# LTCSensorIndex.net
KiCad netlist of a schematic drawn in EAGLE
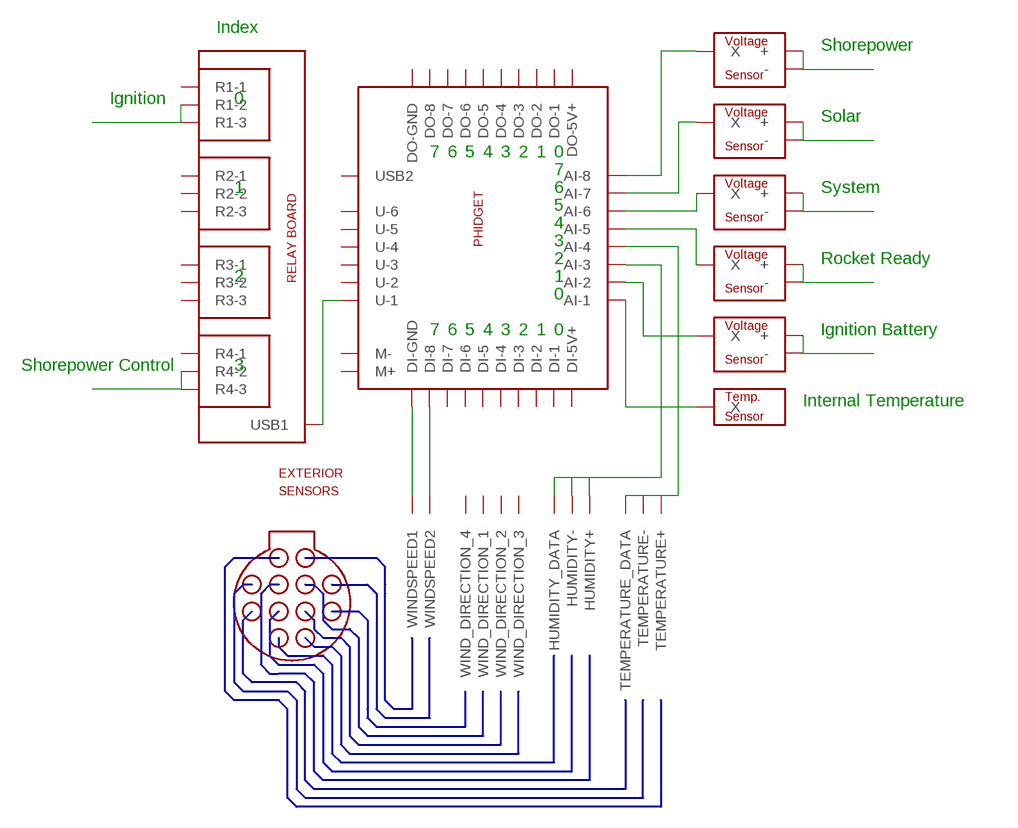
[diagram p0: schematic, sheet 1]

(export (version "E")
  (design (tool "Eeschema 10.0.6"))
  (components
    (comp (ref "U$1")
      (value "LAYOUT-PHIDGET")
      (footprint "eagle-import:LAYOUT-PACKAGE")
      (libsource (lib "eagle-import") (part "LAYOUT-PHIDGET"))
    )
    (comp (ref "U$2")
      (value "LAYOUT-SENSOR-TEMPERATURE")
      (footprint "eagle-import:LAYOUT-PACKAGE")
      (libsource (lib "eagle-import") (part "LAYOUT-SENSOR-TEMPERATURE"))
    )
    (comp (ref "U$3")
      (value "LAYOUT-SENSOR-VOLTAGE")
      (footprint "eagle-import:LAYOUT-PACKAGE")
      (libsource (lib "eagle-import") (part "LAYOUT-SENSOR-VOLTAGE"))
    )
    (comp (ref "U$4")
      (value "LAYOUT-SENSOR-VOLTAGE")
      (footprint "eagle-import:LAYOUT-PACKAGE")
      (libsource (lib "eagle-import") (part "LAYOUT-SENSOR-VOLTAGE"))
    )
    (comp (ref "U$5")
      (value "LAYOUT-SENSOR-VOLTAGE")
      (footprint "eagle-import:LAYOUT-PACKAGE")
      (libsource (lib "eagle-import") (part "LAYOUT-SENSOR-VOLTAGE"))
    )
    (comp (ref "U$6")
      (value "LAYOUT-SENSOR-VOLTAGE")
      (footprint "eagle-import:LAYOUT-PACKAGE")
      (libsource (lib "eagle-import") (part "LAYOUT-SENSOR-VOLTAGE"))
    )
    (comp (ref "U$7")
      (value "LAYOUT-SENSOR-VOLTAGE")
      (footprint "eagle-import:LAYOUT-PACKAGE")
      (libsource (lib "eagle-import") (part "LAYOUT-SENSOR-VOLTAGE"))
    )
    (comp (ref "U$8")
      (value "LAYOUT-RELAY-BOARD")
      (footprint "eagle-import:LAYOUT-PACKAGE")
      (libsource (lib "eagle-import") (part "LAYOUT-RELAY-BOARD"))
    )
    (comp (ref "U$9")
      (value "LAYOUT-LEMO-12PIN")
      (footprint "eagle-import:LEMO-12")
      (libsource (lib "eagle-import") (part "LAYOUT-LEMO-12PIN"))
    )
  )
  (nets
    (net (code "1") (name "Net-(U$1-AI-1)") (class "Default")
      (node (ref "U$1") (pin "P$1") (pinfunction "AI-1_P$1") (pintype "bidirectional"))
      (node (ref "U$2") (pin "P$1") (pinfunction "X_P$1") (pintype "bidirectional"))
    )
    (net (code "2") (name "Net-(U$1-AI-2)") (class "Default")
      (node (ref "U$1") (pin "P$2") (pinfunction "AI-2_P$2") (pintype "bidirectional"))
      (node (ref "U$6") (pin "P$3") (pinfunction "X_P$3") (pintype "bidirectional"))
    )
    (net (code "3") (name "Net-(U$1-AI-3)") (class "Default")
      (node (ref "U$1") (pin "P$3") (pinfunction "AI-3_P$3") (pintype "bidirectional"))
      (node (ref "U$9") (pin "P12") (pinfunction "HUMIDITY+_P12") (pintype "bidirectional"))
      (node (ref "U$9") (pin "P2") (pinfunction "HUMIDITY_DATA_P2") (pintype "bidirectional"))
      (node (ref "U$9") (pin "P9") (pinfunction "HUMIDITY-_P9") (pintype "bidirectional"))
    )
    (net (code "4") (name "Net-(U$1-AI-4)") (class "Default")
      (node (ref "U$1") (pin "P$4") (pinfunction "AI-4_P$4") (pintype "bidirectional"))
      (node (ref "U$9") (pin "P7") (pinfunction "TEMPERATURE_DATA_P7") (pintype "bidirectional"))
    )
    (net (code "5") (name "Net-(U$1-AI-5)") (class "Default")
      (node (ref "U$1") (pin "P$5") (pinfunction "AI-5_P$5") (pintype "bidirectional"))
      (node (ref "U$5") (pin "P$3") (pinfunction "X_P$3") (pintype "bidirectional"))
    )
    (net (code "6") (name "Net-(U$1-AI-6)") (class "Default")
      (node (ref "U$1") (pin "P$6") (pinfunction "AI-6_P$6") (pintype "bidirectional"))
      (node (ref "U$4") (pin "P$3") (pinfunction "X_P$3") (pintype "bidirectional"))
    )
    (net (code "7") (name "Net-(U$1-AI-7)") (class "Default")
      (node (ref "U$1") (pin "P$7") (pinfunction "AI-7_P$7") (pintype "bidirectional"))
      (node (ref "U$3") (pin "P$3") (pinfunction "X_P$3") (pintype "bidirectional"))
    )
    (net (code "8") (name "Net-(U$1-AI-8)") (class "Default")
      (node (ref "U$1") (pin "P$8") (pinfunction "AI-8_P$8") (pintype "bidirectional"))
      (node (ref "U$7") (pin "P$3") (pinfunction "X_P$3") (pintype "bidirectional"))
    )
    (net (code "9") (name "Net-(U$1-DI-8)") (class "Default")
      (node (ref "U$1") (pin "P$17") (pinfunction "DI-8_P$17") (pintype "bidirectional"))
      (node (ref "U$9") (pin "P5") (pinfunction "WINDSPEED2_P5") (pintype "bidirectional"))
    )
    (net (code "10") (name "Net-(U$1-DI-GND)") (class "Default")
      (node (ref "U$1") (pin "P$18") (pinfunction "DI-GND_P$18") (pintype "bidirectional"))
      (node (ref "U$9") (pin "P6") (pinfunction "WINDSPEED1_P6") (pintype "bidirectional"))
    )
    (net (code "11") (name "Net-(U$1-U-1)") (class "Default")
      (node (ref "U$1") (pin "P$31") (pinfunction "U-1_P$31") (pintype "bidirectional"))
      (node (ref "U$8") (pin "P$12") (pinfunction "USB1_P$12") (pintype "bidirectional"))
    )
    (net (code "12") (name "Net-(U$3-+)") (class "Default")
      (node (ref "U$3") (pin "P$1") (pinfunction "+_P$1") (pintype "bidirectional"))
      (node (ref "U$3") (pin "P$2") (pinfunction "-_P$2") (pintype "bidirectional"))
    )
    (net (code "13") (name "Net-(U$4-+)") (class "Default")
      (node (ref "U$4") (pin "P$1") (pinfunction "+_P$1") (pintype "bidirectional"))
      (node (ref "U$4") (pin "P$2") (pinfunction "-_P$2") (pintype "bidirectional"))
    )
    (net (code "14") (name "Net-(U$5-+)") (class "Default")
      (node (ref "U$5") (pin "P$1") (pinfunction "+_P$1") (pintype "bidirectional"))
      (node (ref "U$5") (pin "P$2") (pinfunction "-_P$2") (pintype "bidirectional"))
    )
    (net (code "15") (name "Net-(U$6-+)") (class "Default")
      (node (ref "U$6") (pin "P$1") (pinfunction "+_P$1") (pintype "bidirectional"))
      (node (ref "U$6") (pin "P$2") (pinfunction "-_P$2") (pintype "bidirectional"))
    )
    (net (code "16") (name "Net-(U$7-+)") (class "Default")
      (node (ref "U$7") (pin "P$1") (pinfunction "+_P$1") (pintype "bidirectional"))
      (node (ref "U$7") (pin "P$2") (pinfunction "-_P$2") (pintype "bidirectional"))
    )
    (net (code "17") (name "Net-(U$8-R1-2)") (class "Default")
      (node (ref "U$8") (pin "P$22") (pinfunction "R1-3_P$22") (pintype "bidirectional"))
      (node (ref "U$8") (pin "P$23") (pinfunction "R1-2_P$23") (pintype "bidirectional"))
    )
    (net (code "18") (name "Net-(U$8-R4-2)") (class "Default")
      (node (ref "U$8") (pin "P$13") (pinfunction "R4-3_P$13") (pintype "bidirectional"))
      (node (ref "U$8") (pin "P$14") (pinfunction "R4-2_P$14") (pintype "bidirectional"))
    )
    (net (code "19") (name "unconnected-(U$1-DI-1-PadP$9)") (class "Default")
      (node (ref "U$1") (pin "P$9") (pinfunction "DI-1_P$9") (pintype "bidirectional"))
    )
    (net (code "20") (name "unconnected-(U$1-DI-2-PadP$10)") (class "Default")
      (node (ref "U$1") (pin "P$10") (pinfunction "DI-2_P$10") (pintype "bidirectional"))
    )
    (net (code "21") (name "unconnected-(U$1-DI-3-PadP$11)") (class "Default")
      (node (ref "U$1") (pin "P$11") (pinfunction "DI-3_P$11") (pintype "bidirectional"))
    )
    (net (code "22") (name "unconnected-(U$1-DI-4-PadP$12)") (class "Default")
      (node (ref "U$1") (pin "P$12") (pinfunction "DI-4_P$12") (pintype "bidirectional"))
    )
    (net (code "23") (name "unconnected-(U$1-DI-5-PadP$13)") (class "Default")
      (node (ref "U$1") (pin "P$13") (pinfunction "DI-5_P$13") (pintype "bidirectional"))
    )
    (net (code "24") (name "unconnected-(U$1-DI-5V+-PadP$14)") (class "Default")
      (node (ref "U$1") (pin "P$14") (pinfunction "DI-5V+_P$14") (pintype "bidirectional"))
    )
    (net (code "25") (name "unconnected-(U$1-DI-6-PadP$15)") (class "Default")
      (node (ref "U$1") (pin "P$15") (pinfunction "DI-6_P$15") (pintype "bidirectional"))
    )
    (net (code "26") (name "unconnected-(U$1-DI-7-PadP$16)") (class "Default")
      (node (ref "U$1") (pin "P$16") (pinfunction "DI-7_P$16") (pintype "bidirectional"))
    )
    (net (code "27") (name "unconnected-(U$1-DO-1-PadP$19)") (class "Default")
      (node (ref "U$1") (pin "P$19") (pinfunction "DO-1_P$19") (pintype "bidirectional"))
    )
    (net (code "28") (name "unconnected-(U$1-DO-2-PadP$20)") (class "Default")
      (node (ref "U$1") (pin "P$20") (pinfunction "DO-2_P$20") (pintype "bidirectional"))
    )
    (net (code "29") (name "unconnected-(U$1-DO-3-PadP$21)") (class "Default")
      (node (ref "U$1") (pin "P$21") (pinfunction "DO-3_P$21") (pintype "bidirectional"))
    )
    (net (code "30") (name "unconnected-(U$1-DO-4-PadP$22)") (class "Default")
      (node (ref "U$1") (pin "P$22") (pinfunction "DO-4_P$22") (pintype "bidirectional"))
    )
    (net (code "31") (name "unconnected-(U$1-DO-5-PadP$23)") (class "Default")
      (node (ref "U$1") (pin "P$23") (pinfunction "DO-5_P$23") (pintype "bidirectional"))
    )
    (net (code "32") (name "unconnected-(U$1-DO-5V+-PadP$24)") (class "Default")
      (node (ref "U$1") (pin "P$24") (pinfunction "DO-5V+_P$24") (pintype "bidirectional"))
    )
    (net (code "33") (name "unconnected-(U$1-DO-6-PadP$25)") (class "Default")
      (node (ref "U$1") (pin "P$25") (pinfunction "DO-6_P$25") (pintype "bidirectional"))
    )
    (net (code "34") (name "unconnected-(U$1-DO-7-PadP$26)") (class "Default")
      (node (ref "U$1") (pin "P$26") (pinfunction "DO-7_P$26") (pintype "bidirectional"))
    )
    (net (code "35") (name "unconnected-(U$1-DO-8-PadP$27)") (class "Default")
      (node (ref "U$1") (pin "P$27") (pinfunction "DO-8_P$27") (pintype "bidirectional"))
    )
    (net (code "36") (name "unconnected-(U$1-DO-GND-PadP$28)") (class "Default")
      (node (ref "U$1") (pin "P$28") (pinfunction "DO-GND_P$28") (pintype "bidirectional"))
    )
    (net (code "37") (name "unconnected-(U$1-M+-PadP$29)") (class "Default")
      (node (ref "U$1") (pin "P$29") (pinfunction "M+_P$29") (pintype "bidirectional"))
    )
    (net (code "38") (name "unconnected-(U$1-M--PadP$30)") (class "Default")
      (node (ref "U$1") (pin "P$30") (pinfunction "M-_P$30") (pintype "bidirectional"))
    )
    (net (code "39") (name "unconnected-(U$1-U-2-PadP$32)") (class "Default")
      (node (ref "U$1") (pin "P$32") (pinfunction "U-2_P$32") (pintype "bidirectional"))
    )
    (net (code "40") (name "unconnected-(U$1-U-3-PadP$33)") (class "Default")
      (node (ref "U$1") (pin "P$33") (pinfunction "U-3_P$33") (pintype "bidirectional"))
    )
    (net (code "41") (name "unconnected-(U$1-U-4-PadP$34)") (class "Default")
      (node (ref "U$1") (pin "P$34") (pinfunction "U-4_P$34") (pintype "bidirectional"))
    )
    (net (code "42") (name "unconnected-(U$1-U-5-PadP$35)") (class "Default")
      (node (ref "U$1") (pin "P$35") (pinfunction "U-5_P$35") (pintype "bidirectional"))
    )
    (net (code "43") (name "unconnected-(U$1-U-6-PadP$36)") (class "Default")
      (node (ref "U$1") (pin "P$36") (pinfunction "U-6_P$36") (pintype "bidirectional"))
    )
    (net (code "44") (name "unconnected-(U$1-USB2-PadP$37)") (class "Default")
      (node (ref "U$1") (pin "P$37") (pinfunction "USB2_P$37") (pintype "bidirectional"))
    )
    (net (code "45") (name "unconnected-(U$8-R1-1-PadP$24)") (class "Default")
      (node (ref "U$8") (pin "P$24") (pinfunction "R1-1_P$24") (pintype "bidirectional"))
    )
    (net (code "46") (name "unconnected-(U$8-R2-1-PadP$21)") (class "Default")
      (node (ref "U$8") (pin "P$21") (pinfunction "R2-1_P$21") (pintype "bidirectional"))
    )
    (net (code "47") (name "unconnected-(U$8-R2-2-PadP$20)") (class "Default")
      (node (ref "U$8") (pin "P$20") (pinfunction "R2-2_P$20") (pintype "bidirectional"))
    )
    (net (code "48") (name "unconnected-(U$8-R2-3-PadP$19)") (class "Default")
      (node (ref "U$8") (pin "P$19") (pinfunction "R2-3_P$19") (pintype "bidirectional"))
    )
    (net (code "49") (name "unconnected-(U$8-R3-1-PadP$18)") (class "Default")
      (node (ref "U$8") (pin "P$18") (pinfunction "R3-1_P$18") (pintype "bidirectional"))
    )
    (net (code "50") (name "unconnected-(U$8-R3-2-PadP$17)") (class "Default")
      (node (ref "U$8") (pin "P$17") (pinfunction "R3-2_P$17") (pintype "bidirectional"))
    )
    (net (code "51") (name "unconnected-(U$8-R3-3-PadP$16)") (class "Default")
      (node (ref "U$8") (pin "P$16") (pinfunction "R3-3_P$16") (pintype "bidirectional"))
    )
    (net (code "52") (name "unconnected-(U$8-R4-1-PadP$15)") (class "Default")
      (node (ref "U$8") (pin "P$15") (pinfunction "R4-1_P$15") (pintype "bidirectional"))
    )
    (net (code "53") (name "unconnected-(U$9-TEMPERATURE+-PadP1)") (class "Default")
      (node (ref "U$9") (pin "P1") (pinfunction "TEMPERATURE+_P1") (pintype "bidirectional"))
    )
    (net (code "54") (name "unconnected-(U$9-TEMPERATURE--PadP8)") (class "Default")
      (node (ref "U$9") (pin "P8") (pinfunction "TEMPERATURE-_P8") (pintype "bidirectional"))
    )
    (net (code "55") (name "unconnected-(U$9-WIND_DIRECTION_1-PadP11)") (class "Default")
      (node (ref "U$9") (pin "P11") (pinfunction "WIND_DIRECTION_1_P11") (pintype "bidirectional"))
    )
    (net (code "56") (name "unconnected-(U$9-WIND_DIRECTION_2-PadP10)") (class "Default")
      (node (ref "U$9") (pin "P10") (pinfunction "WIND_DIRECTION_2_P10") (pintype "bidirectional"))
    )
    (net (code "57") (name "unconnected-(U$9-WIND_DIRECTION_3-PadP3)") (class "Default")
      (node (ref "U$9") (pin "P3") (pinfunction "WIND_DIRECTION_3_P3") (pintype "bidirectional"))
    )
    (net (code "58") (name "unconnected-(U$9-WIND_DIRECTION_4-PadP4)") (class "Default")
      (node (ref "U$9") (pin "P4") (pinfunction "WIND_DIRECTION_4_P4") (pintype "bidirectional"))
    )
  )
)
